# VoltageFeedbackSwitch.net
KiCad netlist of a schematic drawn in Altium Designer
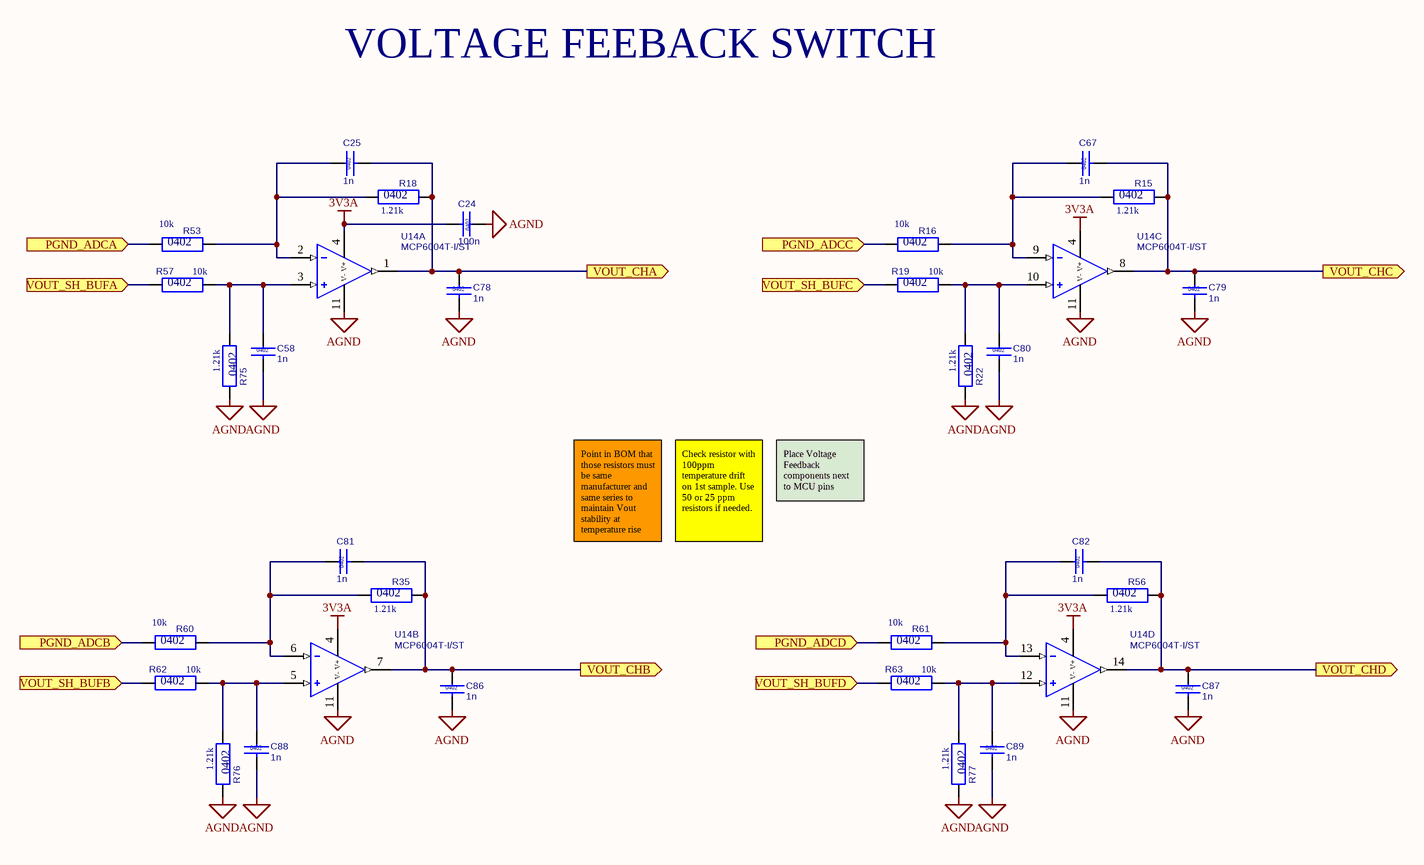
[diagram p0: VoltageFeedbackSwitch.SchDoc]

(export (version "E")
  (design (tool "Eeschema 10.0.6"))
  (components
    (comp (ref "C24")
      (value "100n")
      (footprint "CC0402M")
      (description "Chip ceramic capacitor")
      (fields
        (field (name "CASE") "0402")
        (field (name "PARTNUMBER") "CC0402K-X7R-25V-100N-M")
        (field (name "MANUFACTURER") "Murata")
        (field (name "PUBLISHER") "alexey.savchenko")
      )
      (libsource (lib "AltiumLib") (part "Capacitor_nonpolar"))
    )
    (comp (ref "C25")
      (value "1n")
      (footprint "CC0402M")
      (description "Chip ceramic capacitor")
      (fields
        (field (name "CASE") "0402")
        (field (name "PARTNUMBER") "CC0402J-NP0-50V-1N-M")
        (field (name "MANUFACTURER") "Samsung")
        (field (name "PUBLISHER") "alexey.savchenko")
      )
      (libsource (lib "AltiumLib") (part "Capacitor_nonpolar"))
    )
    (comp (ref "C58")
      (value "1n")
      (footprint "CC0402M")
      (description "Chip ceramic capacitor")
      (fields
        (field (name "CASE") "0402")
        (field (name "PARTNUMBER") "CC0402J-NP0-50V-1N-M")
        (field (name "MANUFACTURER") "Samsung")
        (field (name "PUBLISHER") "alexey.savchenko")
      )
      (libsource (lib "AltiumLib") (part "Capacitor_nonpolar"))
    )
    (comp (ref "C67")
      (value "1n")
      (footprint "CC0402M")
      (description "Chip ceramic capacitor")
      (fields
        (field (name "CASE") "0402")
        (field (name "PARTNUMBER") "CC0402J-NP0-50V-1N-M")
        (field (name "MANUFACTURER") "Samsung")
        (field (name "PUBLISHER") "alexey.savchenko")
      )
      (libsource (lib "AltiumLib") (part "Capacitor_nonpolar"))
    )
    (comp (ref "C78")
      (value "1n")
      (footprint "CC0402M")
      (description "Chip ceramic capacitor")
      (fields
        (field (name "CASE") "0402")
        (field (name "PARTNUMBER") "CC0402K-X7R-50V-1N-M")
        (field (name "MANUFACTURER") "Yageo")
        (field (name "PUBLISHER") "alexey.savchenko")
      )
      (libsource (lib "AltiumLib") (part "Capacitor_nonpolar"))
    )
    (comp (ref "C79")
      (value "1n")
      (footprint "CC0402M")
      (description "Chip ceramic capacitor")
      (fields
        (field (name "CASE") "0402")
        (field (name "PARTNUMBER") "CC0402K-X7R-50V-1N-M")
        (field (name "MANUFACTURER") "Yageo")
        (field (name "PUBLISHER") "alexey.savchenko")
      )
      (libsource (lib "AltiumLib") (part "Capacitor_nonpolar"))
    )
    (comp (ref "C80")
      (value "1n")
      (footprint "CC0402M")
      (description "Chip ceramic capacitor")
      (fields
        (field (name "CASE") "0402")
        (field (name "PARTNUMBER") "CC0402J-NP0-50V-1N-M")
        (field (name "MANUFACTURER") "Samsung")
        (field (name "PUBLISHER") "alexey.savchenko")
      )
      (libsource (lib "AltiumLib") (part "Capacitor_nonpolar"))
    )
    (comp (ref "C81")
      (value "1n")
      (footprint "CC0402M")
      (description "Chip ceramic capacitor")
      (fields
        (field (name "CASE") "0402")
        (field (name "PARTNUMBER") "CC0402J-NP0-50V-1N-M")
        (field (name "MANUFACTURER") "Samsung")
        (field (name "PUBLISHER") "alexey.savchenko")
      )
      (libsource (lib "AltiumLib") (part "Capacitor_nonpolar"))
    )
    (comp (ref "C82")
      (value "1n")
      (footprint "CC0402M")
      (description "Chip ceramic capacitor")
      (fields
        (field (name "CASE") "0402")
        (field (name "PARTNUMBER") "CC0402J-NP0-50V-1N-M")
        (field (name "MANUFACTURER") "Samsung")
        (field (name "PUBLISHER") "alexey.savchenko")
      )
      (libsource (lib "AltiumLib") (part "Capacitor_nonpolar"))
    )
    (comp (ref "C86")
      (value "1n")
      (footprint "CC0402M")
      (description "Chip ceramic capacitor")
      (fields
        (field (name "CASE") "0402")
        (field (name "PARTNUMBER") "CC0402K-X7R-50V-1N-M")
        (field (name "MANUFACTURER") "Yageo")
        (field (name "PUBLISHER") "alexey.savchenko")
      )
      (libsource (lib "AltiumLib") (part "Capacitor_nonpolar"))
    )
    (comp (ref "C87")
      (value "1n")
      (footprint "CC0402M")
      (description "Chip ceramic capacitor")
      (fields
        (field (name "CASE") "0402")
        (field (name "PARTNUMBER") "CC0402K-X7R-50V-1N-M")
        (field (name "MANUFACTURER") "Yageo")
        (field (name "PUBLISHER") "alexey.savchenko")
      )
      (libsource (lib "AltiumLib") (part "Capacitor_nonpolar"))
    )
    (comp (ref "C88")
      (value "1n")
      (footprint "CC0402M")
      (description "Chip ceramic capacitor")
      (fields
        (field (name "CASE") "0402")
        (field (name "PARTNUMBER") "CC0402J-NP0-50V-1N-M")
        (field (name "MANUFACTURER") "Samsung")
        (field (name "PUBLISHER") "alexey.savchenko")
      )
      (libsource (lib "AltiumLib") (part "Capacitor_nonpolar"))
    )
    (comp (ref "C89")
      (value "1n")
      (footprint "CC0402M")
      (description "Chip ceramic capacitor")
      (fields
        (field (name "CASE") "0402")
        (field (name "PARTNUMBER") "CC0402J-NP0-50V-1N-M")
        (field (name "MANUFACTURER") "Samsung")
        (field (name "PUBLISHER") "alexey.savchenko")
      )
      (libsource (lib "AltiumLib") (part "Capacitor_nonpolar"))
    )
    (comp (ref "R15")
      (value "1.21k")
      (footprint "RC0402M")
      (description "Chip resistor")
      (fields
        (field (name "CASE") "0402")
        (field (name "PARTNUMBER") "RC0402F-1K21-M")
        (field (name "MANUFACTURER") "Yageo")
        (field (name "PUBLISHER") "alexey.savchenko")
      )
      (libsource (lib "AltiumLib") (part "Resistor"))
    )
    (comp (ref "R16")
      (value "10k")
      (footprint "RC0402M")
      (description "Chip resistor")
      (fields
        (field (name "CASE") "0402")
        (field (name "PARTNUMBER") "RC0402F-10K-M")
        (field (name "MANUFACTURER") "Yageo")
        (field (name "PUBLISHER") "alexey.savchenko")
      )
      (libsource (lib "AltiumLib") (part "Resistor"))
    )
    (comp (ref "R18")
      (value "1.21k")
      (footprint "RC0402M")
      (description "Chip resistor")
      (fields
        (field (name "CASE") "0402")
        (field (name "PARTNUMBER") "RC0402F-1K21-M")
        (field (name "MANUFACTURER") "Yageo")
        (field (name "PUBLISHER") "alexey.savchenko")
      )
      (libsource (lib "AltiumLib") (part "Resistor"))
    )
    (comp (ref "R19")
      (value "10k")
      (footprint "RC0402M")
      (description "Chip resistor")
      (fields
        (field (name "CASE") "0402")
        (field (name "PARTNUMBER") "RC0402F-10K-M")
        (field (name "MANUFACTURER") "Yageo")
        (field (name "PUBLISHER") "alexey.savchenko")
      )
      (libsource (lib "AltiumLib") (part "Resistor"))
    )
    (comp (ref "R22")
      (value "1.21k")
      (footprint "RC0402M")
      (description "Chip resistor")
      (fields
        (field (name "CASE") "0402")
        (field (name "PARTNUMBER") "RC0402F-1K21-M")
        (field (name "MANUFACTURER") "Yageo")
        (field (name "PUBLISHER") "alexey.savchenko")
      )
      (libsource (lib "AltiumLib") (part "Resistor"))
    )
    (comp (ref "R35")
      (value "1.21k")
      (footprint "RC0402M")
      (description "Chip resistor")
      (fields
        (field (name "CASE") "0402")
        (field (name "PARTNUMBER") "RC0402F-1K21-M")
        (field (name "MANUFACTURER") "Yageo")
        (field (name "PUBLISHER") "alexey.savchenko")
      )
      (libsource (lib "AltiumLib") (part "Resistor"))
    )
    (comp (ref "R53")
      (value "10k")
      (footprint "RC0402M")
      (description "Chip resistor")
      (fields
        (field (name "CASE") "0402")
        (field (name "PARTNUMBER") "RC0402F-10K-M")
        (field (name "MANUFACTURER") "Yageo")
        (field (name "PUBLISHER") "alexey.savchenko")
      )
      (libsource (lib "AltiumLib") (part "Resistor"))
    )
    (comp (ref "R56")
      (value "1.21k")
      (footprint "RC0402M")
      (description "Chip resistor")
      (fields
        (field (name "CASE") "0402")
        (field (name "PARTNUMBER") "RC0402F-1K21-M")
        (field (name "MANUFACTURER") "Yageo")
        (field (name "PUBLISHER") "alexey.savchenko")
      )
      (libsource (lib "AltiumLib") (part "Resistor"))
    )
    (comp (ref "R57")
      (value "10k")
      (footprint "RC0402M")
      (description "Chip resistor")
      (fields
        (field (name "CASE") "0402")
        (field (name "PARTNUMBER") "RC0402F-10K-M")
        (field (name "MANUFACTURER") "Yageo")
        (field (name "PUBLISHER") "alexey.savchenko")
      )
      (libsource (lib "AltiumLib") (part "Resistor"))
    )
    (comp (ref "R60")
      (value "10k")
      (footprint "RC0402M")
      (description "Chip resistor")
      (fields
        (field (name "CASE") "0402")
        (field (name "PARTNUMBER") "RC0402F-10K-M")
        (field (name "MANUFACTURER") "Yageo")
        (field (name "PUBLISHER") "alexey.savchenko")
      )
      (libsource (lib "AltiumLib") (part "Resistor"))
    )
    (comp (ref "R61")
      (value "10k")
      (footprint "RC0402M")
      (description "Chip resistor")
      (fields
        (field (name "CASE") "0402")
        (field (name "PARTNUMBER") "RC0402F-10K-M")
        (field (name "MANUFACTURER") "Yageo")
        (field (name "PUBLISHER") "alexey.savchenko")
      )
      (libsource (lib "AltiumLib") (part "Resistor"))
    )
    (comp (ref "R62")
      (value "10k")
      (footprint "RC0402M")
      (description "Chip resistor")
      (fields
        (field (name "CASE") "0402")
        (field (name "PARTNUMBER") "RC0402F-10K-M")
        (field (name "MANUFACTURER") "Yageo")
        (field (name "PUBLISHER") "alexey.savchenko")
      )
      (libsource (lib "AltiumLib") (part "Resistor"))
    )
    (comp (ref "R63")
      (value "10k")
      (footprint "RC0402M")
      (description "Chip resistor")
      (fields
        (field (name "CASE") "0402")
        (field (name "PARTNUMBER") "RC0402F-10K-M")
        (field (name "MANUFACTURER") "Yageo")
        (field (name "PUBLISHER") "alexey.savchenko")
      )
      (libsource (lib "AltiumLib") (part "Resistor"))
    )
    (comp (ref "R75")
      (value "1.21k")
      (footprint "RC0402M")
      (description "Chip resistor")
      (fields
        (field (name "CASE") "0402")
        (field (name "PARTNUMBER") "RC0402F-1K21-M")
        (field (name "MANUFACTURER") "Yageo")
        (field (name "PUBLISHER") "alexey.savchenko")
      )
      (libsource (lib "AltiumLib") (part "Resistor"))
    )
    (comp (ref "R76")
      (value "1.21k")
      (footprint "RC0402M")
      (description "Chip resistor")
      (fields
        (field (name "CASE") "0402")
        (field (name "PARTNUMBER") "RC0402F-1K21-M")
        (field (name "MANUFACTURER") "Yageo")
        (field (name "PUBLISHER") "alexey.savchenko")
      )
      (libsource (lib "AltiumLib") (part "Resistor"))
    )
    (comp (ref "R77")
      (value "1.21k")
      (footprint "RC0402M")
      (description "Chip resistor")
      (fields
        (field (name "CASE") "0402")
        (field (name "PARTNUMBER") "RC0402F-1K21-M")
        (field (name "MANUFACTURER") "Yageo")
        (field (name "PUBLISHER") "alexey.savchenko")
      )
      (libsource (lib "AltiumLib") (part "Resistor"))
    )
    (comp (ref "U14")
      (value "MCP6004T-I/ST")
      (footprint "TSSOP-14")
      (description "General Purpose Amplifier 4 Circuit Rail-to-Rail 14-TSSOP")
      (fields (field (name "MANUFACTURER") "Microchip") (field (name "PUBLISHER") "alexey.savchenko"))
      (libsource (lib "AltiumLib") (part "LMV324A"))
    )
  )
  (nets
    (net (code "1") (name "/PGND_ADCA") (class "Default")
      (node (ref "R53") (pin "2") (pinfunction "2_2") (pintype "passive"))
    )
    (net (code "2") (name "/PGND_ADCB") (class "Default")
      (node (ref "R60") (pin "2") (pinfunction "2_2") (pintype "passive"))
    )
    (net (code "3") (name "/PGND_ADCC") (class "Default")
      (node (ref "R16") (pin "2") (pinfunction "2_2") (pintype "passive"))
    )
    (net (code "4") (name "/PGND_ADCD") (class "Default")
      (node (ref "R61") (pin "2") (pinfunction "2_2") (pintype "passive"))
    )
    (net (code "5") (name "/VOUT_CHA") (class "Default")
      (node (ref "C25") (pin "2") (pinfunction "2_2") (pintype "passive"))
      (node (ref "C78") (pin "1") (pinfunction "1_1") (pintype "passive"))
      (node (ref "R18") (pin "1") (pinfunction "1_1") (pintype "passive"))
      (node (ref "U14") (pin "1") (pinfunction "OUT1_1") (pintype "output"))
    )
    (net (code "6") (name "/VOUT_CHB") (class "Default")
      (node (ref "C81") (pin "2") (pinfunction "2_2") (pintype "passive"))
      (node (ref "C86") (pin "1") (pinfunction "1_1") (pintype "passive"))
      (node (ref "R35") (pin "1") (pinfunction "1_1") (pintype "passive"))
      (node (ref "U14") (pin "7") (pinfunction "OUT2_7") (pintype "output"))
    )
    (net (code "7") (name "/VOUT_CHC") (class "Default")
      (node (ref "C67") (pin "2") (pinfunction "2_2") (pintype "passive"))
      (node (ref "C79") (pin "1") (pinfunction "1_1") (pintype "passive"))
      (node (ref "R15") (pin "1") (pinfunction "1_1") (pintype "passive"))
      (node (ref "U14") (pin "8") (pinfunction "OUT3_8") (pintype "output"))
    )
    (net (code "8") (name "/VOUT_CHD") (class "Default")
      (node (ref "C82") (pin "2") (pinfunction "2_2") (pintype "passive"))
      (node (ref "C87") (pin "1") (pinfunction "1_1") (pintype "passive"))
      (node (ref "R56") (pin "1") (pinfunction "1_1") (pintype "passive"))
      (node (ref "U14") (pin "14") (pinfunction "OUT4_14") (pintype "output"))
    )
    (net (code "9") (name "/VOUT_SH_BUFA") (class "Default")
      (node (ref "R57") (pin "2") (pinfunction "2_2") (pintype "passive"))
    )
    (net (code "10") (name "/VOUT_SH_BUFB") (class "Default")
      (node (ref "R62") (pin "2") (pinfunction "2_2") (pintype "passive"))
    )
    (net (code "11") (name "/VOUT_SH_BUFC") (class "Default")
      (node (ref "R19") (pin "2") (pinfunction "2_2") (pintype "passive"))
    )
    (net (code "12") (name "/VOUT_SH_BUFD") (class "Default")
      (node (ref "R63") (pin "2") (pinfunction "2_2") (pintype "passive"))
    )
    (net (code "13") (name "3V3A") (class "Default")
      (node (ref "C24") (pin "2") (pinfunction "2_2") (pintype "passive"))
      (node (ref "U14") (pin "4") (pinfunction "V+_4") (pintype "power_in"))
    )
    (net (code "14") (name "AGND") (class "Default")
      (node (ref "C24") (pin "1") (pinfunction "1_1") (pintype "passive"))
      (node (ref "C58") (pin "2") (pinfunction "2_2") (pintype "passive"))
      (node (ref "C78") (pin "2") (pinfunction "2_2") (pintype "passive"))
      (node (ref "C79") (pin "2") (pinfunction "2_2") (pintype "passive"))
      (node (ref "C80") (pin "2") (pinfunction "2_2") (pintype "passive"))
      (node (ref "C86") (pin "2") (pinfunction "2_2") (pintype "passive"))
      (node (ref "C87") (pin "2") (pinfunction "2_2") (pintype "passive"))
      (node (ref "C88") (pin "2") (pinfunction "2_2") (pintype "passive"))
      (node (ref "C89") (pin "2") (pinfunction "2_2") (pintype "passive"))
      (node (ref "R22") (pin "1") (pinfunction "1_1") (pintype "passive"))
      (node (ref "R75") (pin "1") (pinfunction "1_1") (pintype "passive"))
      (node (ref "R76") (pin "1") (pinfunction "1_1") (pintype "passive"))
      (node (ref "R77") (pin "1") (pinfunction "1_1") (pintype "passive"))
      (node (ref "U14") (pin "11") (pinfunction "V-_11") (pintype "power_in"))
    )
    (net (code "15") (name "Net-(U14A-IN1+)") (class "Default")
      (node (ref "C58") (pin "1") (pinfunction "1_1") (pintype "passive"))
      (node (ref "R57") (pin "1") (pinfunction "1_1") (pintype "passive"))
      (node (ref "R75") (pin "2") (pinfunction "2_2") (pintype "passive"))
      (node (ref "U14") (pin "3") (pinfunction "IN1+_3") (pintype "input"))
    )
    (net (code "16") (name "Net-(U14A-IN1-)") (class "Default")
      (node (ref "C25") (pin "1") (pinfunction "1_1") (pintype "passive"))
      (node (ref "R18") (pin "2") (pinfunction "2_2") (pintype "passive"))
      (node (ref "R53") (pin "1") (pinfunction "1_1") (pintype "passive"))
      (node (ref "U14") (pin "2") (pinfunction "IN1-_2") (pintype "input"))
    )
    (net (code "17") (name "Net-(U14B-IN2+)") (class "Default")
      (node (ref "C88") (pin "1") (pinfunction "1_1") (pintype "passive"))
      (node (ref "R62") (pin "1") (pinfunction "1_1") (pintype "passive"))
      (node (ref "R76") (pin "2") (pinfunction "2_2") (pintype "passive"))
      (node (ref "U14") (pin "5") (pinfunction "IN2+_5") (pintype "input"))
    )
    (net (code "18") (name "Net-(U14B-IN2-)") (class "Default")
      (node (ref "C81") (pin "1") (pinfunction "1_1") (pintype "passive"))
      (node (ref "R35") (pin "2") (pinfunction "2_2") (pintype "passive"))
      (node (ref "R60") (pin "1") (pinfunction "1_1") (pintype "passive"))
      (node (ref "U14") (pin "6") (pinfunction "IN2-_6") (pintype "input"))
    )
    (net (code "19") (name "Net-(U14C-IN3+)") (class "Default")
      (node (ref "C80") (pin "1") (pinfunction "1_1") (pintype "passive"))
      (node (ref "R19") (pin "1") (pinfunction "1_1") (pintype "passive"))
      (node (ref "R22") (pin "2") (pinfunction "2_2") (pintype "passive"))
      (node (ref "U14") (pin "10") (pinfunction "IN3+_10") (pintype "input"))
    )
    (net (code "20") (name "Net-(U14C-IN3-)") (class "Default")
      (node (ref "C67") (pin "1") (pinfunction "1_1") (pintype "passive"))
      (node (ref "R15") (pin "2") (pinfunction "2_2") (pintype "passive"))
      (node (ref "R16") (pin "1") (pinfunction "1_1") (pintype "passive"))
      (node (ref "U14") (pin "9") (pinfunction "IN3-_9") (pintype "input"))
    )
    (net (code "21") (name "Net-(U14D-IN4+)") (class "Default")
      (node (ref "C89") (pin "1") (pinfunction "1_1") (pintype "passive"))
      (node (ref "R63") (pin "1") (pinfunction "1_1") (pintype "passive"))
      (node (ref "R77") (pin "2") (pinfunction "2_2") (pintype "passive"))
      (node (ref "U14") (pin "12") (pinfunction "IN4+_12") (pintype "input"))
    )
    (net (code "22") (name "Net-(U14D-IN4-)") (class "Default")
      (node (ref "C82") (pin "1") (pinfunction "1_1") (pintype "passive"))
      (node (ref "R56") (pin "2") (pinfunction "2_2") (pintype "passive"))
      (node (ref "R61") (pin "1") (pinfunction "1_1") (pintype "passive"))
      (node (ref "U14") (pin "13") (pinfunction "IN4-_13") (pintype "input"))
    )
  )
)
